# jellyFish_v1.net
KiCad netlist of a schematic drawn in EAGLE
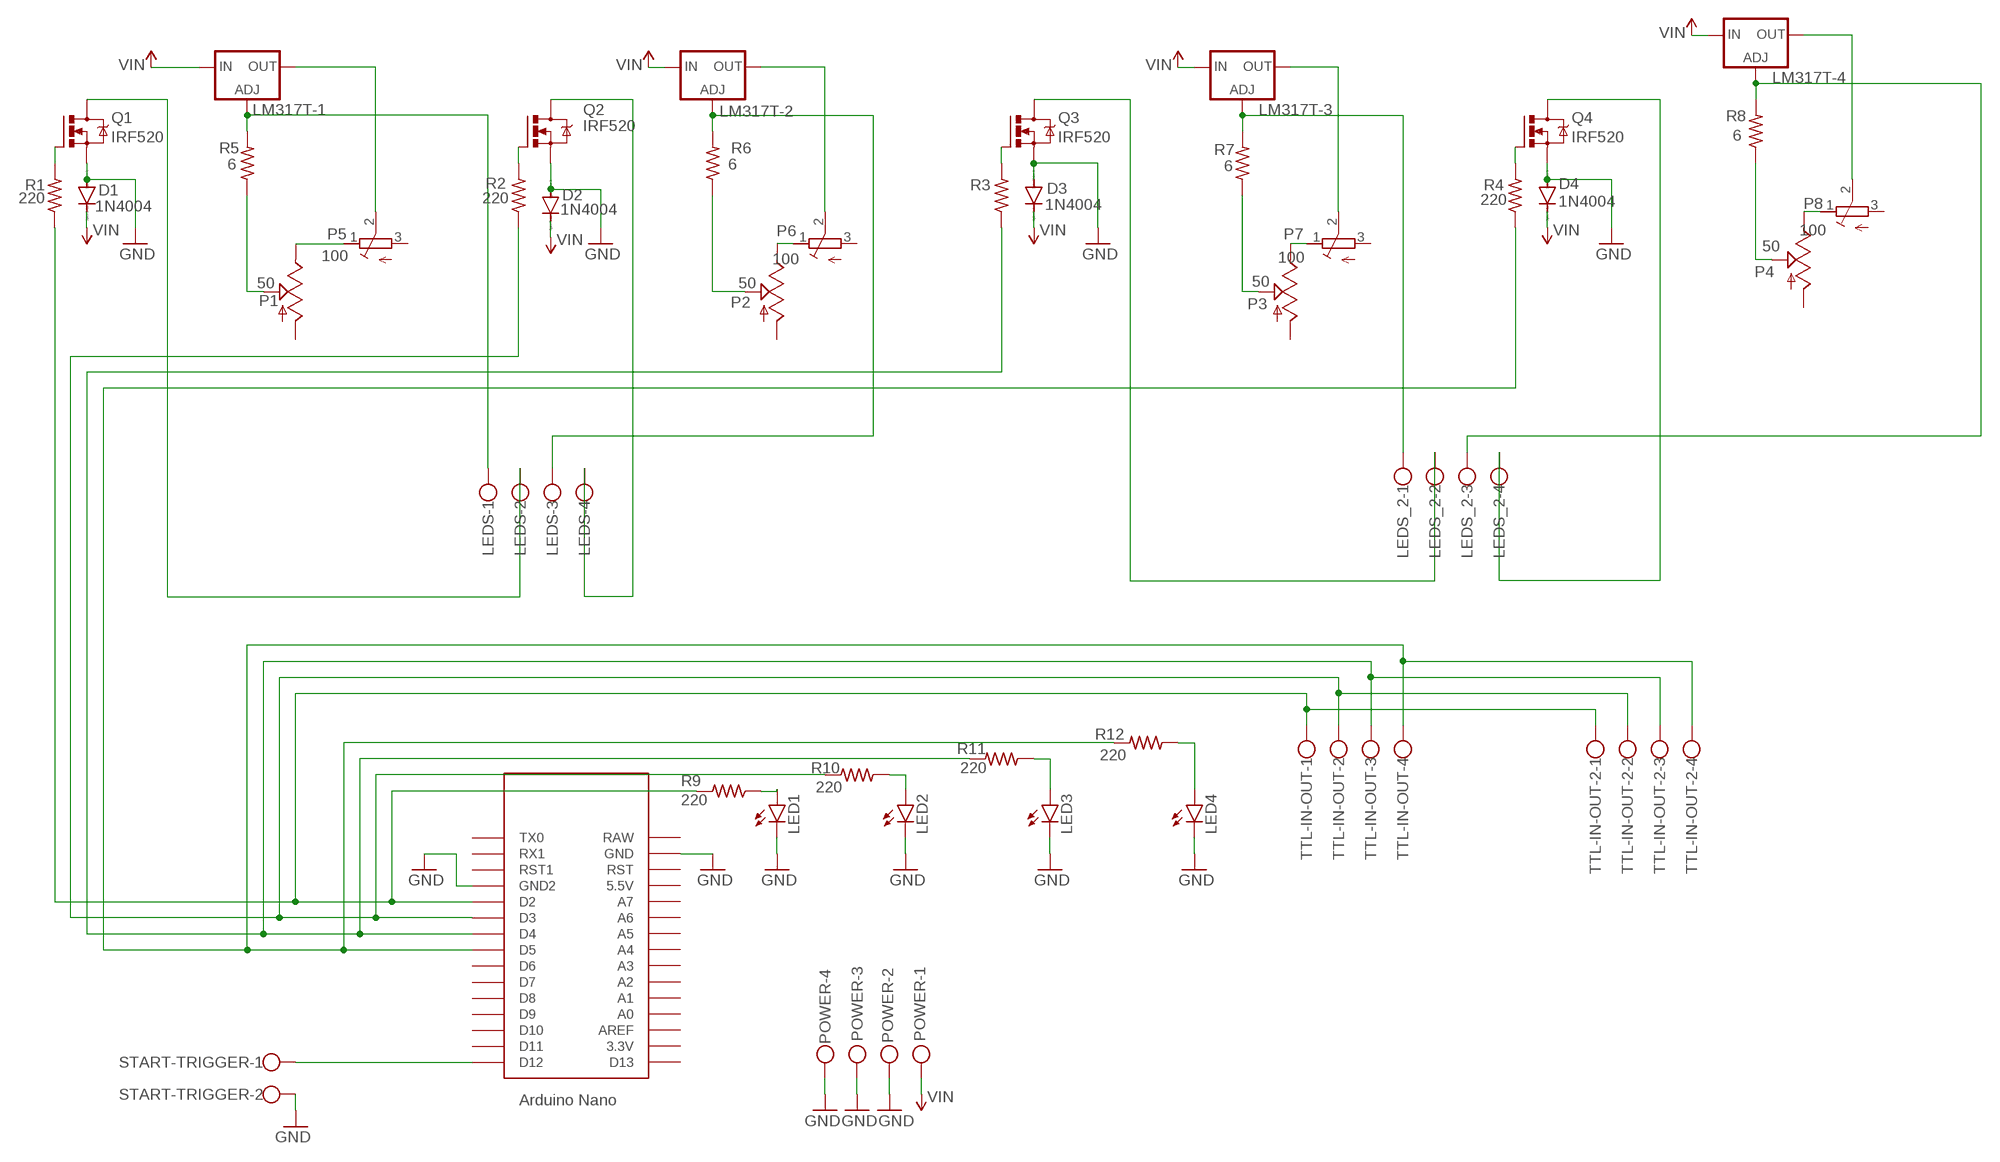
[diagram p0: schematic, sheet 1]

(export (version "E")
  (design (tool "Eeschema 10.0.6"))
  (components
    (comp (ref "D1")
      (value "1N4004")
      (footprint "eagle-import:DO41-10")
      (libsource (lib "eagle-import") (part "1N4004"))
    )
    (comp (ref "D2")
      (value "1N4004")
      (footprint "eagle-import:DO41-10")
      (libsource (lib "eagle-import") (part "1N4004"))
    )
    (comp (ref "D3")
      (value "1N4004")
      (footprint "eagle-import:DO41-10")
      (libsource (lib "eagle-import") (part "1N4004"))
    )
    (comp (ref "D4")
      (value "1N4004")
      (footprint "eagle-import:DO41-10")
      (libsource (lib "eagle-import") (part "1N4004"))
    )
    (comp (ref "LED1")
      (value "LEDCHIPLED_0805")
      (footprint "eagle-import:CHIPLED_0805")
      (libsource (lib "eagle-import") (part "LEDCHIPLED_0805"))
    )
    (comp (ref "LED2")
      (value "LEDCHIPLED_0805")
      (footprint "eagle-import:CHIPLED_0805")
      (libsource (lib "eagle-import") (part "LEDCHIPLED_0805"))
    )
    (comp (ref "LED3")
      (value "LEDCHIPLED_0805")
      (footprint "eagle-import:CHIPLED_0805")
      (libsource (lib "eagle-import") (part "LEDCHIPLED_0805"))
    )
    (comp (ref "LED4")
      (value "LEDCHIPLED_0805")
      (footprint "eagle-import:CHIPLED_0805")
      (libsource (lib "eagle-import") (part "LEDCHIPLED_0805"))
    )
    (comp (ref "LEDS")
      (value "W237-4")
      (footprint "eagle-import:W237-4")
      (libsource (lib "eagle-import") (part "W237-4"))
    )
    (comp (ref "LEDS_2")
      (value "W237-4")
      (footprint "eagle-import:W237-4")
      (libsource (lib "eagle-import") (part "W237-4"))
    )
    (comp (ref "LM317T-1")
      (value "LM317TS")
      (footprint "eagle-import:317TS")
      (libsource (lib "eagle-import") (part "LM317TS"))
    )
    (comp (ref "LM317T-2")
      (value "LM317TS")
      (footprint "eagle-import:317TS")
      (libsource (lib "eagle-import") (part "LM317TS"))
    )
    (comp (ref "LM317T-3")
      (value "LM317TS")
      (footprint "eagle-import:317TS")
      (libsource (lib "eagle-import") (part "LM317TS"))
    )
    (comp (ref "LM317T-4")
      (value "LM317TS")
      (footprint "eagle-import:317TS")
      (libsource (lib "eagle-import") (part "LM317TS"))
    )
    (comp (ref "P1")
      (value "50")
      (footprint "eagle-import:S63P")
      (libsource (lib "eagle-import") (part "TRIM_US-S63P"))
    )
    (comp (ref "P2")
      (value "50")
      (footprint "eagle-import:S63P")
      (libsource (lib "eagle-import") (part "TRIM_US-S63P"))
    )
    (comp (ref "P3")
      (value "50")
      (footprint "eagle-import:S63P")
      (libsource (lib "eagle-import") (part "TRIM_US-S63P"))
    )
    (comp (ref "P4")
      (value "50")
      (footprint "eagle-import:S63P")
      (libsource (lib "eagle-import") (part "TRIM_US-S63P"))
    )
    (comp (ref "P5")
      (value "100")
      (footprint "eagle-import:RTRIMT93YA")
      (libsource (lib "eagle-import") (part "R-TRIMMT93YA"))
    )
    (comp (ref "P6")
      (value "100")
      (footprint "eagle-import:RTRIMT93YA")
      (libsource (lib "eagle-import") (part "R-TRIMMT93YA"))
    )
    (comp (ref "P7")
      (value "100")
      (footprint "eagle-import:RTRIMT93YA")
      (libsource (lib "eagle-import") (part "R-TRIMMT93YA"))
    )
    (comp (ref "P8")
      (value "100")
      (footprint "eagle-import:RTRIMT93YA")
      (libsource (lib "eagle-import") (part "R-TRIMMT93YA"))
    )
    (comp (ref "POWER")
      (value "W237-4")
      (footprint "eagle-import:W237-4")
      (libsource (lib "eagle-import") (part "W237-4"))
    )
    (comp (ref "Q1")
      (value "IRF520")
      (footprint "eagle-import:TO220BV")
      (libsource (lib "eagle-import") (part "IRF520"))
    )
    (comp (ref "Q2")
      (value "IRF520")
      (footprint "eagle-import:TO220BV")
      (libsource (lib "eagle-import") (part "IRF520"))
    )
    (comp (ref "Q3")
      (value "IRF520")
      (footprint "eagle-import:TO220BV")
      (libsource (lib "eagle-import") (part "IRF520"))
    )
    (comp (ref "Q4")
      (value "IRF520")
      (footprint "eagle-import:TO220BV")
      (libsource (lib "eagle-import") (part "IRF520"))
    )
    (comp (ref "R1")
      (value "220")
      (footprint "eagle-import:R0805")
      (libsource (lib "eagle-import") (part "R-US_R0805"))
    )
    (comp (ref "R2")
      (value "220")
      (footprint "eagle-import:R0805")
      (libsource (lib "eagle-import") (part "R-US_R0805"))
    )
    (comp (ref "R3")
      (value "220")
      (footprint "eagle-import:R0805")
      (libsource (lib "eagle-import") (part "R-US_R0805"))
    )
    (comp (ref "R4")
      (value "220")
      (footprint "eagle-import:R0805")
      (libsource (lib "eagle-import") (part "R-US_R0805"))
    )
    (comp (ref "R5")
      (value "6")
      (footprint "eagle-import:R0805")
      (libsource (lib "eagle-import") (part "R-US_R0805"))
    )
    (comp (ref "R6")
      (value "6")
      (footprint "eagle-import:R0805")
      (libsource (lib "eagle-import") (part "R-US_R0805"))
    )
    (comp (ref "R7")
      (value "6")
      (footprint "eagle-import:R0805")
      (libsource (lib "eagle-import") (part "R-US_R0805"))
    )
    (comp (ref "R8")
      (value "6")
      (footprint "eagle-import:R0805")
      (libsource (lib "eagle-import") (part "R-US_R0805"))
    )
    (comp (ref "R9")
      (value "220")
      (footprint "eagle-import:R0805")
      (libsource (lib "eagle-import") (part "R-US_R0805"))
    )
    (comp (ref "R10")
      (value "220")
      (footprint "eagle-import:R0805")
      (libsource (lib "eagle-import") (part "R-US_R0805"))
    )
    (comp (ref "R11")
      (value "220")
      (footprint "eagle-import:R0805")
      (libsource (lib "eagle-import") (part "R-US_R0805"))
    )
    (comp (ref "R12")
      (value "220")
      (footprint "eagle-import:R0805")
      (libsource (lib "eagle-import") (part "R-US_R0805"))
    )
    (comp (ref "START-TRIGGER")
      (value "W237-102")
      (footprint "eagle-import:W237-102")
      (fields (field (name "MPN") "237-102"))
      (libsource (lib "eagle-import") (part "W237-102"))
    )
    (comp (ref "TTL-IN-OUT")
      (value "W237-4")
      (footprint "eagle-import:W237-4")
      (libsource (lib "eagle-import") (part "W237-4"))
    )
    (comp (ref "TTL-IN-OUT-2")
      (value "W237-4")
      (footprint "eagle-import:W237-4")
      (libsource (lib "eagle-import") (part "W237-4"))
    )
    (comp (ref "U$1")
      (value "NANO")
      (footprint "eagle-import:NANO")
      (libsource (lib "eagle-import") (part "NANO"))
    )
  )
  (nets
    (net (code "1") (name "GND") (class "Default")
      (node (ref "D1") (pin "A") (pinfunction "A_A") (pintype "passive"))
      (node (ref "D2") (pin "A") (pinfunction "A_A") (pintype "passive"))
      (node (ref "D3") (pin "A") (pinfunction "A_A") (pintype "passive"))
      (node (ref "D4") (pin "A") (pinfunction "A_A") (pintype "passive"))
      (node (ref "LED1") (pin "C") (pinfunction "C_C") (pintype "passive"))
      (node (ref "LED2") (pin "C") (pinfunction "C_C") (pintype "passive"))
      (node (ref "LED3") (pin "C") (pinfunction "C_C") (pintype "passive"))
      (node (ref "LED4") (pin "C") (pinfunction "C_C") (pintype "passive"))
      (node (ref "POWER") (pin "2") (pinfunction "KL_2") (pintype "passive"))
      (node (ref "POWER") (pin "3") (pinfunction "KL_3") (pintype "passive"))
      (node (ref "POWER") (pin "4") (pinfunction "KL_4") (pintype "passive"))
      (node (ref "Q1") (pin "S") (pinfunction "S_S") (pintype "passive"))
      (node (ref "Q2") (pin "S") (pinfunction "S_S") (pintype "passive"))
      (node (ref "Q3") (pin "S") (pinfunction "S_S") (pintype "passive"))
      (node (ref "Q4") (pin "S") (pinfunction "S_S") (pintype "passive"))
      (node (ref "START-TRIGGER") (pin "2") (pinfunction "KL_2") (pintype "passive"))
      (node (ref "U$1") (pin "GND") (pinfunction "GND_GND") (pintype "bidirectional"))
      (node (ref "U$1") (pin "GND1") (pinfunction "GND2_GND1") (pintype "bidirectional"))
    )
    (net (code "2") (name "Net-(LED1-PadA)") (class "Default")
      (node (ref "LED1") (pin "A") (pinfunction "A_A") (pintype "passive"))
      (node (ref "R9") (pin "1") (pinfunction "1_1") (pintype "passive"))
    )
    (net (code "3") (name "Net-(LED2-PadA)") (class "Default")
      (node (ref "LED2") (pin "A") (pinfunction "A_A") (pintype "passive"))
      (node (ref "R10") (pin "1") (pinfunction "1_1") (pintype "passive"))
    )
    (net (code "4") (name "Net-(LED3-PadA)") (class "Default")
      (node (ref "LED3") (pin "A") (pinfunction "A_A") (pintype "passive"))
      (node (ref "R11") (pin "1") (pinfunction "1_1") (pintype "passive"))
    )
    (net (code "5") (name "Net-(LED4-PadA)") (class "Default")
      (node (ref "LED4") (pin "A") (pinfunction "A_A") (pintype "passive"))
      (node (ref "R12") (pin "1") (pinfunction "1_1") (pintype "passive"))
    )
    (net (code "6") (name "Net-(LEDSA-KL)") (class "Default")
      (node (ref "LEDS") (pin "1") (pinfunction "KL_1") (pintype "passive"))
      (node (ref "LM317T-1") (pin "1") (pinfunction "ADJ_1") (pintype "input"))
      (node (ref "R5") (pin "2") (pinfunction "2_2") (pintype "passive"))
    )
    (net (code "7") (name "Net-(LEDSB-KL)") (class "Default")
      (node (ref "LEDS") (pin "2") (pinfunction "KL_2") (pintype "passive"))
      (node (ref "Q1") (pin "D") (pinfunction "D_D") (pintype "passive"))
    )
    (net (code "8") (name "Net-(LEDSC-KL)") (class "Default")
      (node (ref "LEDS") (pin "3") (pinfunction "KL_3") (pintype "passive"))
      (node (ref "LM317T-2") (pin "1") (pinfunction "ADJ_1") (pintype "input"))
      (node (ref "R6") (pin "2") (pinfunction "2_2") (pintype "passive"))
    )
    (net (code "9") (name "Net-(LEDSD-KL)") (class "Default")
      (node (ref "LEDS") (pin "4") (pinfunction "KL_4") (pintype "passive"))
      (node (ref "Q2") (pin "D") (pinfunction "D_D") (pintype "passive"))
    )
    (net (code "10") (name "Net-(LEDS_2A-KL)") (class "Default")
      (node (ref "LEDS_2") (pin "1") (pinfunction "KL_1") (pintype "passive"))
      (node (ref "LM317T-3") (pin "1") (pinfunction "ADJ_1") (pintype "input"))
      (node (ref "R7") (pin "2") (pinfunction "2_2") (pintype "passive"))
    )
    (net (code "11") (name "Net-(LEDS_2B-KL)") (class "Default")
      (node (ref "LEDS_2") (pin "2") (pinfunction "KL_2") (pintype "passive"))
      (node (ref "Q3") (pin "D") (pinfunction "D_D") (pintype "passive"))
    )
    (net (code "12") (name "Net-(LEDS_2C-KL)") (class "Default")
      (node (ref "LEDS_2") (pin "3") (pinfunction "KL_3") (pintype "passive"))
      (node (ref "LM317T-4") (pin "1") (pinfunction "ADJ_1") (pintype "input"))
      (node (ref "R8") (pin "2") (pinfunction "2_2") (pintype "passive"))
    )
    (net (code "13") (name "Net-(LEDS_2D-KL)") (class "Default")
      (node (ref "LEDS_2") (pin "4") (pinfunction "KL_4") (pintype "passive"))
      (node (ref "Q4") (pin "D") (pinfunction "D_D") (pintype "passive"))
    )
    (net (code "14") (name "Net-(LM317T-1-OUT)") (class "Default")
      (node (ref "LM317T-1") (pin "2") (pinfunction "OUT_2") (pintype "passive"))
      (node (ref "P5") (pin "2") (pinfunction "S_2") (pintype "passive"))
    )
    (net (code "15") (name "Net-(LM317T-2-OUT)") (class "Default")
      (node (ref "LM317T-2") (pin "2") (pinfunction "OUT_2") (pintype "passive"))
      (node (ref "P6") (pin "2") (pinfunction "S_2") (pintype "passive"))
    )
    (net (code "16") (name "Net-(LM317T-3-OUT)") (class "Default")
      (node (ref "LM317T-3") (pin "2") (pinfunction "OUT_2") (pintype "passive"))
      (node (ref "P7") (pin "2") (pinfunction "S_2") (pintype "passive"))
    )
    (net (code "17") (name "Net-(LM317T-4-OUT)") (class "Default")
      (node (ref "LM317T-4") (pin "2") (pinfunction "OUT_2") (pintype "passive"))
      (node (ref "P8") (pin "2") (pinfunction "S_2") (pintype "passive"))
    )
    (net (code "18") (name "Net-(P1-PadS)") (class "Default")
      (node (ref "P1") (pin "S") (pinfunction "S_S") (pintype "passive"))
      (node (ref "R5") (pin "1") (pinfunction "1_1") (pintype "passive"))
    )
    (net (code "19") (name "Net-(P2-PadS)") (class "Default")
      (node (ref "P2") (pin "S") (pinfunction "S_S") (pintype "passive"))
      (node (ref "R6") (pin "1") (pinfunction "1_1") (pintype "passive"))
    )
    (net (code "20") (name "Net-(P3-PadS)") (class "Default")
      (node (ref "P3") (pin "S") (pinfunction "S_S") (pintype "passive"))
      (node (ref "R7") (pin "1") (pinfunction "1_1") (pintype "passive"))
    )
    (net (code "21") (name "Net-(P4-PadS)") (class "Default")
      (node (ref "P4") (pin "S") (pinfunction "S_S") (pintype "passive"))
      (node (ref "R8") (pin "1") (pinfunction "1_1") (pintype "passive"))
    )
    (net (code "22") (name "Net-(P5-E)") (class "Default")
      (node (ref "P1") (pin "E") (pinfunction "E_E") (pintype "passive"))
      (node (ref "P5") (pin "1") (pinfunction "E_1") (pintype "passive"))
    )
    (net (code "23") (name "Net-(P6-E)") (class "Default")
      (node (ref "P2") (pin "E") (pinfunction "E_E") (pintype "passive"))
      (node (ref "P6") (pin "1") (pinfunction "E_1") (pintype "passive"))
    )
    (net (code "24") (name "Net-(P7-E)") (class "Default")
      (node (ref "P3") (pin "E") (pinfunction "E_E") (pintype "passive"))
      (node (ref "P7") (pin "1") (pinfunction "E_1") (pintype "passive"))
    )
    (net (code "25") (name "Net-(P8-E)") (class "Default")
      (node (ref "P4") (pin "E") (pinfunction "E_E") (pintype "passive"))
      (node (ref "P8") (pin "1") (pinfunction "E_1") (pintype "passive"))
    )
    (net (code "26") (name "Net-(Q1-PadG)") (class "Default")
      (node (ref "Q1") (pin "G") (pinfunction "G_G") (pintype "passive"))
      (node (ref "R1") (pin "2") (pinfunction "2_2") (pintype "passive"))
    )
    (net (code "27") (name "Net-(Q2-PadG)") (class "Default")
      (node (ref "Q2") (pin "G") (pinfunction "G_G") (pintype "passive"))
      (node (ref "R2") (pin "2") (pinfunction "2_2") (pintype "passive"))
    )
    (net (code "28") (name "Net-(Q3-PadG)") (class "Default")
      (node (ref "Q3") (pin "G") (pinfunction "G_G") (pintype "passive"))
      (node (ref "R3") (pin "2") (pinfunction "2_2") (pintype "passive"))
    )
    (net (code "29") (name "Net-(Q4-PadG)") (class "Default")
      (node (ref "Q4") (pin "G") (pinfunction "G_G") (pintype "passive"))
      (node (ref "R4") (pin "2") (pinfunction "2_2") (pintype "passive"))
    )
    (net (code "30") (name "Net-(START-TRIGGERA-KL)") (class "Default")
      (node (ref "START-TRIGGER") (pin "1") (pinfunction "KL_1") (pintype "passive"))
      (node (ref "U$1") (pin "D12") (pinfunction "D12_D12") (pintype "bidirectional"))
    )
    (net (code "31") (name "Net-(TTL-IN-OUT-2A-KL)") (class "Default")
      (node (ref "R1") (pin "1") (pinfunction "1_1") (pintype "passive"))
      (node (ref "R9") (pin "2") (pinfunction "2_2") (pintype "passive"))
      (node (ref "TTL-IN-OUT") (pin "1") (pinfunction "KL_1") (pintype "passive"))
      (node (ref "TTL-IN-OUT-2") (pin "1") (pinfunction "KL_1") (pintype "passive"))
      (node (ref "U$1") (pin "D2") (pinfunction "D2_D2") (pintype "bidirectional"))
    )
    (net (code "32") (name "Net-(TTL-IN-OUT-2B-KL)") (class "Default")
      (node (ref "R10") (pin "2") (pinfunction "2_2") (pintype "passive"))
      (node (ref "R2") (pin "1") (pinfunction "1_1") (pintype "passive"))
      (node (ref "TTL-IN-OUT") (pin "2") (pinfunction "KL_2") (pintype "passive"))
      (node (ref "TTL-IN-OUT-2") (pin "2") (pinfunction "KL_2") (pintype "passive"))
      (node (ref "U$1") (pin "D3") (pinfunction "D3_D3") (pintype "bidirectional"))
    )
    (net (code "33") (name "Net-(TTL-IN-OUT-2C-KL)") (class "Default")
      (node (ref "R11") (pin "2") (pinfunction "2_2") (pintype "passive"))
      (node (ref "R3") (pin "1") (pinfunction "1_1") (pintype "passive"))
      (node (ref "TTL-IN-OUT") (pin "3") (pinfunction "KL_3") (pintype "passive"))
      (node (ref "TTL-IN-OUT-2") (pin "3") (pinfunction "KL_3") (pintype "passive"))
      (node (ref "U$1") (pin "D4") (pinfunction "D4_D4") (pintype "bidirectional"))
    )
    (net (code "34") (name "Net-(TTL-IN-OUT-2D-KL)") (class "Default")
      (node (ref "R12") (pin "2") (pinfunction "2_2") (pintype "passive"))
      (node (ref "R4") (pin "1") (pinfunction "1_1") (pintype "passive"))
      (node (ref "TTL-IN-OUT") (pin "4") (pinfunction "KL_4") (pintype "passive"))
      (node (ref "TTL-IN-OUT-2") (pin "4") (pinfunction "KL_4") (pintype "passive"))
      (node (ref "U$1") (pin "D5") (pinfunction "D5_D5") (pintype "bidirectional"))
    )
    (net (code "35") (name "VIN") (class "Default")
      (node (ref "D1") (pin "C") (pinfunction "C_C") (pintype "passive"))
      (node (ref "D2") (pin "C") (pinfunction "C_C") (pintype "passive"))
      (node (ref "D3") (pin "C") (pinfunction "C_C") (pintype "passive"))
      (node (ref "D4") (pin "C") (pinfunction "C_C") (pintype "passive"))
      (node (ref "LM317T-1") (pin "3") (pinfunction "IN_3") (pintype "input"))
      (node (ref "LM317T-2") (pin "3") (pinfunction "IN_3") (pintype "input"))
      (node (ref "LM317T-3") (pin "3") (pinfunction "IN_3") (pintype "input"))
      (node (ref "LM317T-4") (pin "3") (pinfunction "IN_3") (pintype "input"))
      (node (ref "POWER") (pin "1") (pinfunction "KL_1") (pintype "passive"))
    )
    (net (code "36") (name "unconnected-(P1-PadA)") (class "Default")
      (node (ref "P1") (pin "A") (pinfunction "A_A") (pintype "passive"))
    )
    (net (code "37") (name "unconnected-(P2-PadA)") (class "Default")
      (node (ref "P2") (pin "A") (pinfunction "A_A") (pintype "passive"))
    )
    (net (code "38") (name "unconnected-(P3-PadA)") (class "Default")
      (node (ref "P3") (pin "A") (pinfunction "A_A") (pintype "passive"))
    )
    (net (code "39") (name "unconnected-(P4-PadA)") (class "Default")
      (node (ref "P4") (pin "A") (pinfunction "A_A") (pintype "passive"))
    )
    (net (code "40") (name "unconnected-(P5-A-Pad3)") (class "Default")
      (node (ref "P5") (pin "3") (pinfunction "A_3") (pintype "passive"))
    )
    (net (code "41") (name "unconnected-(P6-A-Pad3)") (class "Default")
      (node (ref "P6") (pin "3") (pinfunction "A_3") (pintype "passive"))
    )
    (net (code "42") (name "unconnected-(P7-A-Pad3)") (class "Default")
      (node (ref "P7") (pin "3") (pinfunction "A_3") (pintype "passive"))
    )
    (net (code "43") (name "unconnected-(P8-A-Pad3)") (class "Default")
      (node (ref "P8") (pin "3") (pinfunction "A_3") (pintype "passive"))
    )
    (net (code "44") (name "unconnected-(U$1-5.5V-Pad5V)") (class "Default")
      (node (ref "U$1") (pin "5V") (pinfunction "5.5V_5V") (pintype "bidirectional"))
    )
    (net (code "45") (name "unconnected-(U$1-Pad3.3V)") (class "Default")
      (node (ref "U$1") (pin "3.3V") (pinfunction "3.3V_3.3V") (pintype "bidirectional"))
    )
    (net (code "46") (name "unconnected-(U$1-PadA0)") (class "Default")
      (node (ref "U$1") (pin "A0") (pinfunction "A0_A0") (pintype "bidirectional"))
    )
    (net (code "47") (name "unconnected-(U$1-PadA1)") (class "Default")
      (node (ref "U$1") (pin "A1") (pinfunction "A1_A1") (pintype "bidirectional"))
    )
    (net (code "48") (name "unconnected-(U$1-PadA2)") (class "Default")
      (node (ref "U$1") (pin "A2") (pinfunction "A2_A2") (pintype "bidirectional"))
    )
    (net (code "49") (name "unconnected-(U$1-PadA3)") (class "Default")
      (node (ref "U$1") (pin "A3") (pinfunction "A3_A3") (pintype "bidirectional"))
    )
    (net (code "50") (name "unconnected-(U$1-PadA4)") (class "Default")
      (node (ref "U$1") (pin "A4") (pinfunction "A4_A4") (pintype "bidirectional"))
    )
    (net (code "51") (name "unconnected-(U$1-PadA5)") (class "Default")
      (node (ref "U$1") (pin "A5") (pinfunction "A5_A5") (pintype "bidirectional"))
    )
    (net (code "52") (name "unconnected-(U$1-PadA6)") (class "Default")
      (node (ref "U$1") (pin "A6") (pinfunction "A6_A6") (pintype "bidirectional"))
    )
    (net (code "53") (name "unconnected-(U$1-PadA7)") (class "Default")
      (node (ref "U$1") (pin "A7") (pinfunction "A7_A7") (pintype "bidirectional"))
    )
    (net (code "54") (name "unconnected-(U$1-PadAREF)") (class "Default")
      (node (ref "U$1") (pin "AREF") (pinfunction "AREF_AREF") (pintype "bidirectional"))
    )
    (net (code "55") (name "unconnected-(U$1-PadD6)") (class "Default")
      (node (ref "U$1") (pin "D6") (pinfunction "D6_D6") (pintype "bidirectional"))
    )
    (net (code "56") (name "unconnected-(U$1-PadD7)") (class "Default")
      (node (ref "U$1") (pin "D7") (pinfunction "D7_D7") (pintype "bidirectional"))
    )
    (net (code "57") (name "unconnected-(U$1-PadD8)") (class "Default")
      (node (ref "U$1") (pin "D8") (pinfunction "D8_D8") (pintype "bidirectional"))
    )
    (net (code "58") (name "unconnected-(U$1-PadD9)") (class "Default")
      (node (ref "U$1") (pin "D9") (pinfunction "D9_D9") (pintype "bidirectional"))
    )
    (net (code "59") (name "unconnected-(U$1-PadD10)") (class "Default")
      (node (ref "U$1") (pin "D10") (pinfunction "D10_D10") (pintype "bidirectional"))
    )
    (net (code "60") (name "unconnected-(U$1-PadD11)") (class "Default")
      (node (ref "U$1") (pin "D11") (pinfunction "D11_D11") (pintype "bidirectional"))
    )
    (net (code "61") (name "unconnected-(U$1-PadD13)") (class "Default")
      (node (ref "U$1") (pin "D13") (pinfunction "D13_D13") (pintype "bidirectional"))
    )
    (net (code "62") (name "unconnected-(U$1-PadICSP1)") (class "Default")
      (node (ref "U$1") (pin "ICSP1") (pinfunction "ICSP1_ICSP1") (pintype "bidirectional"))
    )
    (net (code "63") (name "unconnected-(U$1-PadICSP2)") (class "Default")
      (node (ref "U$1") (pin "ICSP2") (pinfunction "ICSP2_ICSP2") (pintype "bidirectional"))
    )
    (net (code "64") (name "unconnected-(U$1-PadICSP3)") (class "Default")
      (node (ref "U$1") (pin "ICSP3") (pinfunction "ICSP3_ICSP3") (pintype "bidirectional"))
    )
    (net (code "65") (name "unconnected-(U$1-PadICSP4)") (class "Default")
      (node (ref "U$1") (pin "ICSP4") (pinfunction "ICSP4_ICSP4") (pintype "bidirectional"))
    )
    (net (code "66") (name "unconnected-(U$1-PadICSP5)") (class "Default")
      (node (ref "U$1") (pin "ICSP5") (pinfunction "ICSP5_ICSP5") (pintype "bidirectional"))
    )
    (net (code "67") (name "unconnected-(U$1-PadICSP6)") (class "Default")
      (node (ref "U$1") (pin "ICSP6") (pinfunction "ICSP6_ICSP6") (pintype "bidirectional"))
    )
    (net (code "68") (name "unconnected-(U$1-PadRAW)") (class "Default")
      (node (ref "U$1") (pin "RAW") (pinfunction "RAW_RAW") (pintype "bidirectional"))
    )
    (net (code "69") (name "unconnected-(U$1-PadRST)") (class "Default")
      (node (ref "U$1") (pin "RST") (pinfunction "RST_RST") (pintype "bidirectional"))
    )
    (net (code "70") (name "unconnected-(U$1-PadRST1)") (class "Default")
      (node (ref "U$1") (pin "RST1") (pinfunction "RST1_RST1") (pintype "bidirectional"))
    )
    (net (code "71") (name "unconnected-(U$1-PadRX1)") (class "Default")
      (node (ref "U$1") (pin "RX1") (pinfunction "RX1_RX1") (pintype "bidirectional"))
    )
    (net (code "72") (name "unconnected-(U$1-PadTX0)") (class "Default")
      (node (ref "U$1") (pin "TX0") (pinfunction "TX0_TX0") (pintype "bidirectional"))
    )
  )
)
